# Power.net
KiCad netlist of a schematic drawn in Altium Designer
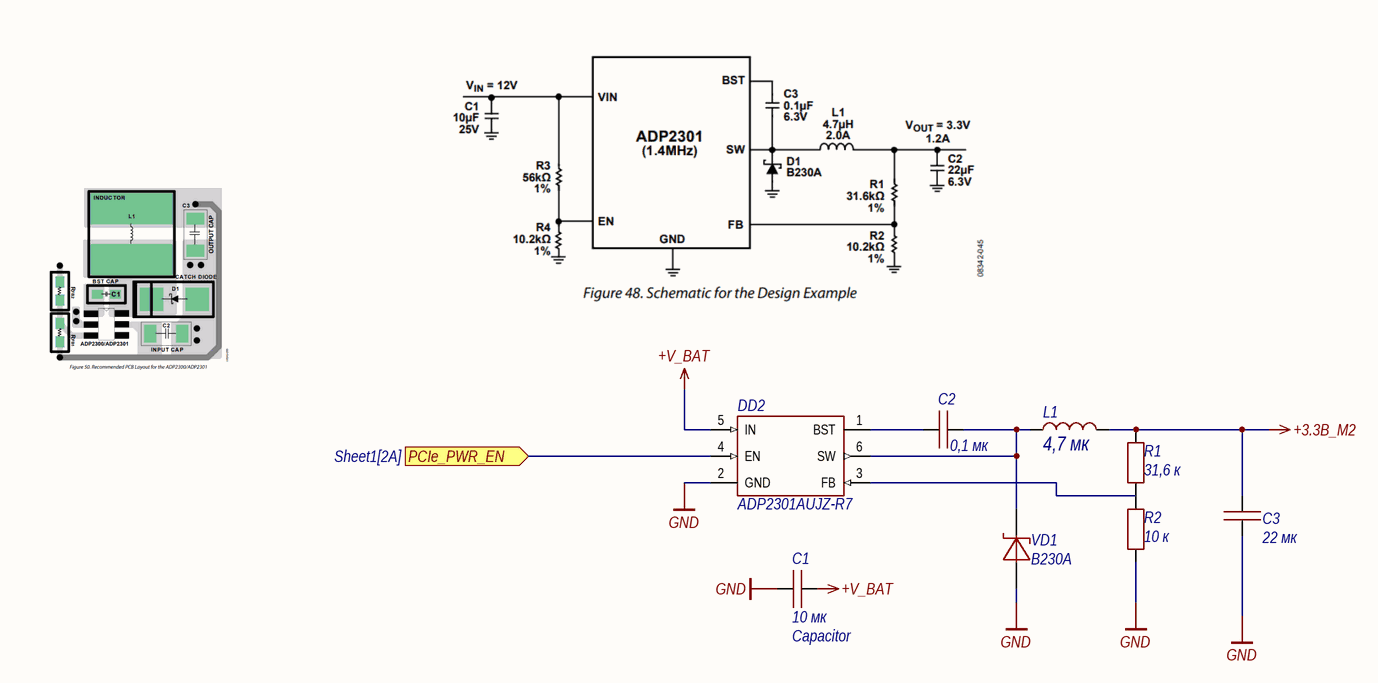
[diagram p0: Power.SchDoc]

(export (version "E")
  (design (tool "Eeschema 10.0.6"))
  (components
    (comp (ref "C1")
      (value "Capacitor")
      (footprint "1210C")
      (description "Конденсатор")
      (fields
        (field (name "ALTIUM_VALUE") "10 мк")
        (field (name "PART NUMBER") "Capacitor_10u_10_35V_X7R_1210C")
        (field (name "TOLERANCE") "0,1")
      )
      (libsource (lib "Hydrolib") (part "Capacitor"))
    )
    (comp (ref "C2")
      (value "0,1 мк")
      (footprint "0603C")
      (description "Конденсатор")
      (fields (field (name "PART NUMBER") "Capacitor_0,1u_10_50V_X7R_0603C") (field (name "TOLERANCE") "0,1"))
      (libsource (lib "Hydrolib") (part "Capacitor"))
    )
    (comp (ref "C3")
      (value "22 мк")
      (footprint "1210C")
      (description "Конденсатор")
      (fields (field (name "PART NUMBER") "Capacitor_22u_10_25V_X7R_1210C") (field (name "TOLERANCE") "0,1"))
      (libsource (lib "Hydrolib") (part "Capacitor"))
    )
    (comp (ref "DD2")
      (value "ADP2301AUJZ-R7")
      (footprint "SOT23-6")
      (description "DC-DC преобразователь понижающий ADJ 1.2А")
      (libsource (lib "Hydrolib") (part "ADP2300"))
    )
    (comp (ref "L1")
      (value "4,7 мк")
      (footprint "IHLP-2525")
      (description "ЧИП-индуктивность экранированная 4,7мкГн ±20% 5,5A 40мОм 2525")
      (fields (field (name "PART NUMBER") "IHLP2525CZER4R7M01"))
      (libsource (lib "Hydrolib") (part "Inductance"))
    )
    (comp (ref "R1")
      (value "31,6 к")
      (footprint "0603R")
      (description "Резистор номиналом 31,6 кОм и точностью 1%")
      (fields (field (name "PART NUMBER") "Resistor_31.6k_1_0603") (field (name "TOLERANCE") "1%"))
      (libsource (lib "") (part "Resistor_1"))
    )
    (comp (ref "R2")
      (value "10 к")
      (footprint "0603R")
      (description "Резистор номиналом 10 кОм и точностью 1%")
      (fields (field (name "PART NUMBER") "Resistor_10k_1_0603") (field (name "TOLERANCE") "1%"))
      (libsource (lib "Hydrolib") (part "Resistor"))
    )
    (comp (ref "VD1")
      (value "B230A")
      (footprint "SMA")
      (description "Диод шоттки на 40 В, ном. ток 2.1 А")
      (fields (field (name "PART NUMBER") "15MQ040N"))
      (libsource (lib "Hydrolib") (part "Schottky_diode"))
    )
  )
  (nets
    (net (code "1") (name "+3.3В_M2") (class "Default")
      (node (ref "C3") (pin "2") (pinfunction "2_2") (pintype "passive"))
      (node (ref "L1") (pin "2") (pinfunction "2_2") (pintype "passive"))
      (node (ref "R1") (pin "1") (pinfunction "1_1") (pintype "passive"))
    )
    (net (code "2") (name "+V_BAT") (class "Default")
      (node (ref "C1") (pin "2") (pinfunction "2_2") (pintype "passive"))
      (node (ref "DD2") (pin "5") (pinfunction "IN_5") (pintype "input"))
    )
    (net (code "3") (name "/PCIe_PWR_EN") (class "Default")
      (node (ref "DD2") (pin "4") (pinfunction "EN_4") (pintype "input"))
    )
    (net (code "4") (name "GND") (class "Default")
      (node (ref "C1") (pin "1") (pinfunction "1_1") (pintype "passive"))
      (node (ref "C3") (pin "1") (pinfunction "1_1") (pintype "passive"))
      (node (ref "DD2") (pin "2") (pinfunction "GND_2") (pintype "power_in"))
      (node (ref "R2") (pin "1") (pinfunction "1_1") (pintype "passive"))
      (node (ref "VD1") (pin "1") (pinfunction "1_1") (pintype "passive"))
    )
    (net (code "5") (name "Net-(DD2-BST)") (class "Default")
      (node (ref "C2") (pin "1") (pinfunction "1_1") (pintype "passive"))
      (node (ref "DD2") (pin "1") (pinfunction "BST_1") (pintype "power_in"))
    )
    (net (code "6") (name "Net-(DD2-FB)") (class "Default")
      (node (ref "DD2") (pin "3") (pinfunction "FB_3") (pintype "input"))
      (node (ref "R1") (pin "2") (pinfunction "2_2") (pintype "passive"))
      (node (ref "R2") (pin "2") (pinfunction "2_2") (pintype "passive"))
    )
    (net (code "7") (name "Net-(DD2-SW)") (class "Default")
      (node (ref "C2") (pin "2") (pinfunction "2_2") (pintype "passive"))
      (node (ref "DD2") (pin "6") (pinfunction "SW_6") (pintype "output"))
      (node (ref "L1") (pin "1") (pinfunction "1_1") (pintype "passive"))
      (node (ref "VD1") (pin "2") (pinfunction "2_2") (pintype "passive"))
    )
  )
)
